# BigBus_XXL_Error.net
KiCad netlist of a schematic drawn in EAGLE
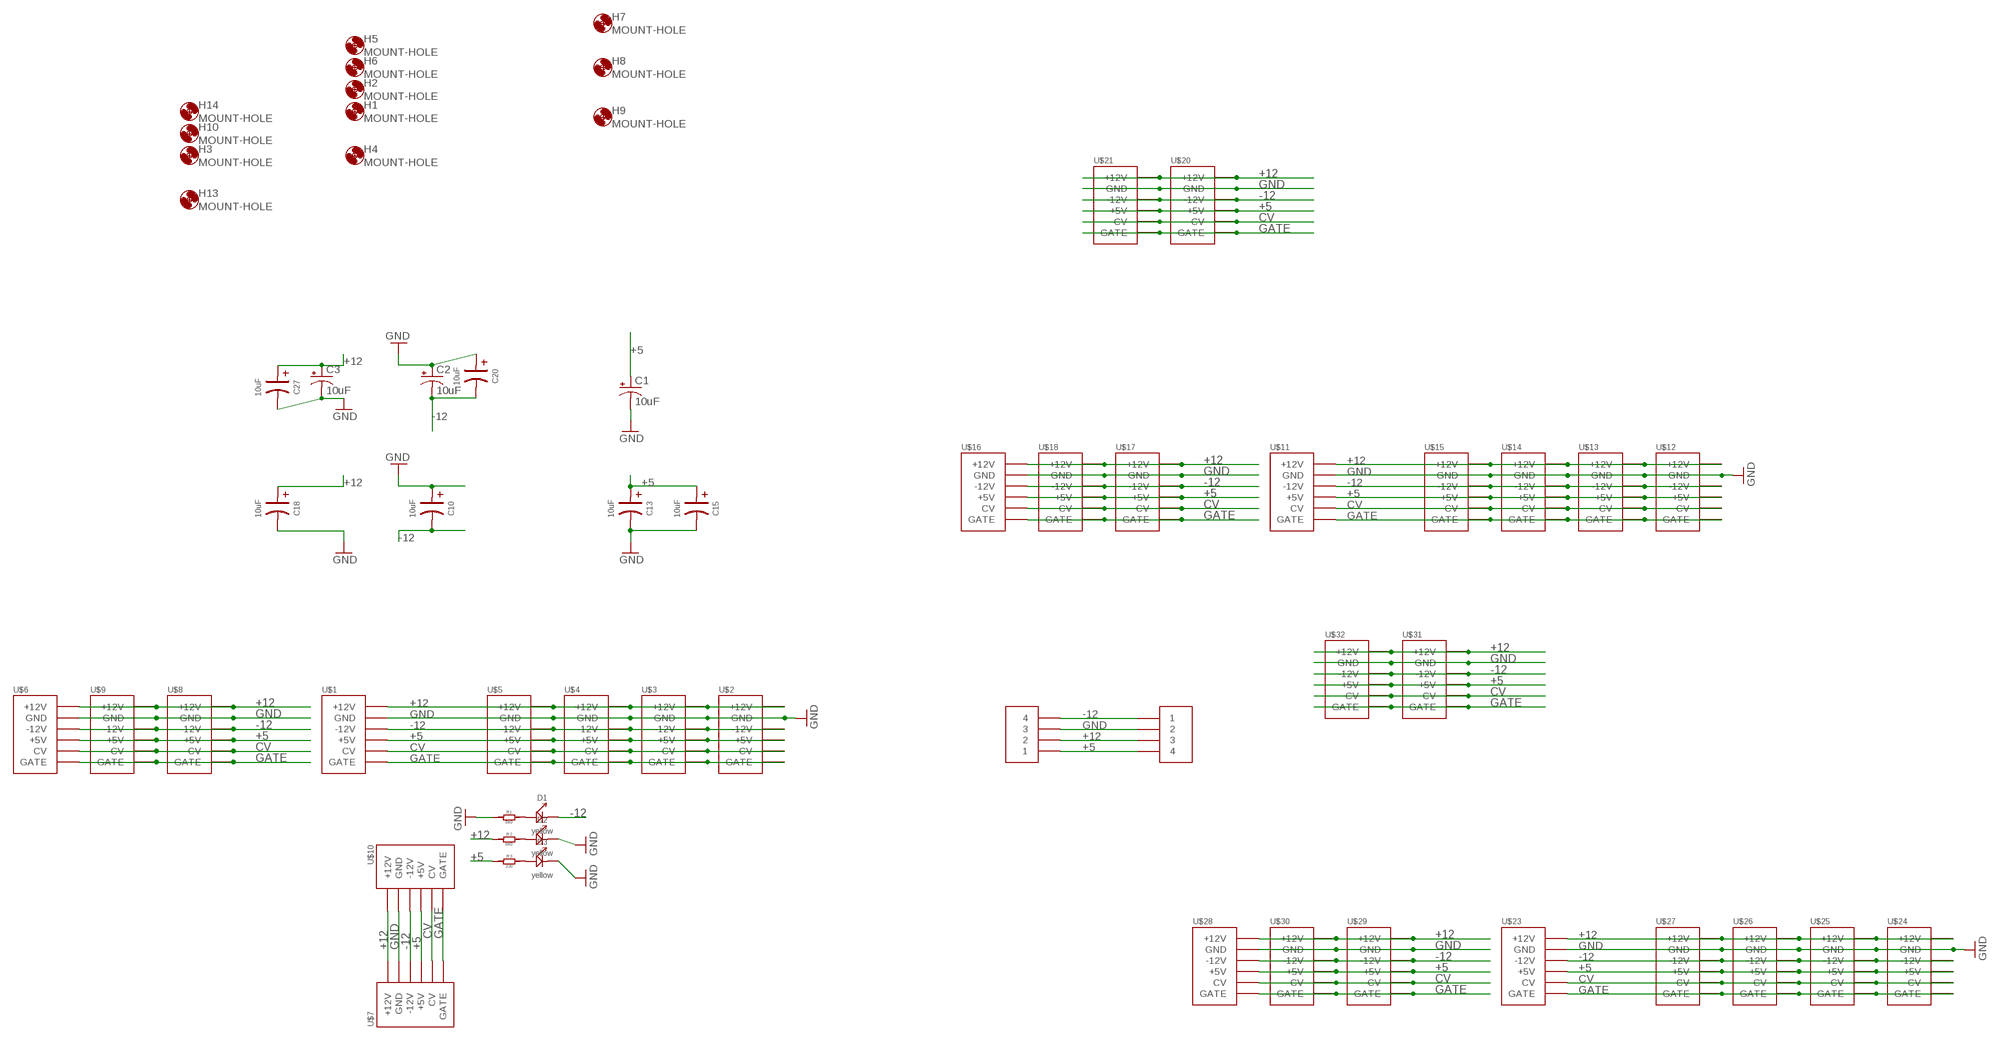
[diagram p0: schematic, sheet 1]

(export (version "E")
  (design (tool "Eeschema 10.0.6"))
  (components
    (comp (ref "C1")
      (value "10uF")
      (footprint "eagle-import:PANASONIC_D")
      (libsource (lib "eagle-import") (part "CAP_POLD"))
    )
    (comp (ref "C2")
      (value "10uF")
      (footprint "eagle-import:PANASONIC_D")
      (libsource (lib "eagle-import") (part "CAP_POLD"))
    )
    (comp (ref "C3")
      (value "10uF")
      (footprint "eagle-import:PANASONIC_D")
      (libsource (lib "eagle-import") (part "CAP_POLD"))
    )
    (comp (ref "C10")
      (value "10uF")
      (footprint "eagle-import:CASE-A_3216")
      (libsource (lib "eagle-import") (part "C-POLAR-A"))
    )
    (comp (ref "C13")
      (value "10uF")
      (footprint "eagle-import:CASE-A_3216")
      (libsource (lib "eagle-import") (part "C-POLAR-A"))
    )
    (comp (ref "C15")
      (value "10uF")
      (footprint "eagle-import:CASE-A_3216")
      (libsource (lib "eagle-import") (part "C-POLAR-A"))
    )
    (comp (ref "C18")
      (value "10uF")
      (footprint "eagle-import:CASE-A_3216")
      (libsource (lib "eagle-import") (part "C-POLAR-A"))
    )
    (comp (ref "C20")
      (value "10uF")
      (footprint "eagle-import:CASE-A_3216")
      (libsource (lib "eagle-import") (part "C-POLAR-A"))
    )
    (comp (ref "C27")
      (value "10uF")
      (footprint "eagle-import:CASE-A_3216")
      (libsource (lib "eagle-import") (part "C-POLAR-A"))
    )
    (comp (ref "D1")
      (value "yellow")
      (footprint "eagle-import:LED0603")
      (libsource (lib "eagle-import") (part "LED"))
    )
    (comp (ref "D2")
      (value "yellow")
      (footprint "eagle-import:LED0603")
      (libsource (lib "eagle-import") (part "LED"))
    )
    (comp (ref "D3")
      (value "yellow")
      (footprint "eagle-import:LED0603")
      (libsource (lib "eagle-import") (part "LED"))
    )
    (comp (ref "H1")
      (value "MOUNT-HOLE")
      (footprint "eagle-import:3.2-NOMARKINGS-SMALLSAFEZONE")
      (libsource (lib "eagle-import") (part "MOUNT-HOLE"))
    )
    (comp (ref "H2")
      (value "MOUNT-HOLE")
      (footprint "eagle-import:3.2-NOMARKINGS-SMALLSAFEZONE")
      (libsource (lib "eagle-import") (part "MOUNT-HOLE"))
    )
    (comp (ref "H3")
      (value "MOUNT-HOLE")
      (footprint "eagle-import:3.2-NOMARKINGS-SMALLSAFEZONE")
      (libsource (lib "eagle-import") (part "MOUNT-HOLE"))
    )
    (comp (ref "H4")
      (value "MOUNT-HOLE")
      (footprint "eagle-import:3.2-NOMARKINGS-SMALLSAFEZONE")
      (libsource (lib "eagle-import") (part "MOUNT-HOLE"))
    )
    (comp (ref "H5")
      (value "MOUNT-HOLE")
      (footprint "eagle-import:3.2-NOMARKINGS-SMALLSAFEZONE")
      (libsource (lib "eagle-import") (part "MOUNT-HOLE"))
    )
    (comp (ref "H6")
      (value "MOUNT-HOLE")
      (footprint "eagle-import:3.2-NOMARKINGS-SMALLSAFEZONE")
      (libsource (lib "eagle-import") (part "MOUNT-HOLE"))
    )
    (comp (ref "H7")
      (value "MOUNT-HOLE")
      (footprint "eagle-import:3.2-NOMARKINGS-SMALLSAFEZONE")
      (libsource (lib "eagle-import") (part "MOUNT-HOLE"))
    )
    (comp (ref "H8")
      (value "MOUNT-HOLE")
      (footprint "eagle-import:3.2-NOMARKINGS-SMALLSAFEZONE")
      (libsource (lib "eagle-import") (part "MOUNT-HOLE"))
    )
    (comp (ref "H9")
      (value "MOUNT-HOLE")
      (footprint "eagle-import:3.2-NOMARKINGS-SMALLSAFEZONE")
      (libsource (lib "eagle-import") (part "MOUNT-HOLE"))
    )
    (comp (ref "H10")
      (value "MOUNT-HOLE")
      (footprint "eagle-import:3.2-NOMARKINGS-SMALLSAFEZONE")
      (libsource (lib "eagle-import") (part "MOUNT-HOLE"))
    )
    (comp (ref "H13")
      (value "MOUNT-HOLE")
      (footprint "eagle-import:3.2-NOMARKINGS-SMALLSAFEZONE")
      (libsource (lib "eagle-import") (part "MOUNT-HOLE"))
    )
    (comp (ref "H14")
      (value "MOUNT-HOLE")
      (footprint "eagle-import:3.2-NOMARKINGS-SMALLSAFEZONE")
      (libsource (lib "eagle-import") (part "MOUNT-HOLE"))
    )
    (comp (ref "R1")
      (value "680")
      (footprint "eagle-import:R0603")
      (libsource (lib "eagle-import") (part "R-0603"))
    )
    (comp (ref "R2")
      (value "680")
      (footprint "eagle-import:R0603")
      (libsource (lib "eagle-import") (part "R-0603"))
    )
    (comp (ref "R3")
      (value "220")
      (footprint "eagle-import:R0603")
      (libsource (lib "eagle-import") (part "R-0603"))
    )
    (comp (ref "U$1")
      (value "POWER_SHROUDED_NOTEXT")
      (footprint "eagle-import:POWER_16_SHROUDED_NOTEXT")
      (libsource (lib "eagle-import") (part "POWER_SHROUDED_NOTEXT"))
    )
    (comp (ref "U$2")
      (value "POWER_SHROUDED_NOTEXT")
      (footprint "eagle-import:POWER_16_SHROUDED_NOTEXT")
      (libsource (lib "eagle-import") (part "POWER_SHROUDED_NOTEXT"))
    )
    (comp (ref "U$3")
      (value "POWER_SHROUDED_NOTEXT")
      (footprint "eagle-import:POWER_16_SHROUDED_NOTEXT")
      (libsource (lib "eagle-import") (part "POWER_SHROUDED_NOTEXT"))
    )
    (comp (ref "U$4")
      (value "POWER_SHROUDED_NOTEXT")
      (footprint "eagle-import:POWER_16_SHROUDED_NOTEXT")
      (libsource (lib "eagle-import") (part "POWER_SHROUDED_NOTEXT"))
    )
    (comp (ref "U$5")
      (value "POWER_SHROUDED_NOTEXT")
      (footprint "eagle-import:POWER_16_SHROUDED_NOTEXT")
      (libsource (lib "eagle-import") (part "POWER_SHROUDED_NOTEXT"))
    )
    (comp (ref "U$6")
      (value "POWER_SHROUDED_NOTEXT")
      (footprint "eagle-import:POWER_16_SHROUDED_NOTEXT")
      (libsource (lib "eagle-import") (part "POWER_SHROUDED_NOTEXT"))
    )
    (comp (ref "U$7")
      (value "POWER_SHROUDED_NOTEXT")
      (footprint "eagle-import:POWER_16_SHROUDED_NOTEXT")
      (libsource (lib "eagle-import") (part "POWER_SHROUDED_NOTEXT"))
    )
    (comp (ref "U$8")
      (value "POWER_SHROUDED_NOTEXT")
      (footprint "eagle-import:POWER_16_SHROUDED_NOTEXT")
      (libsource (lib "eagle-import") (part "POWER_SHROUDED_NOTEXT"))
    )
    (comp (ref "U$9")
      (value "POWER_SHROUDED_NOTEXT")
      (footprint "eagle-import:POWER_16_SHROUDED_NOTEXT")
      (libsource (lib "eagle-import") (part "POWER_SHROUDED_NOTEXT"))
    )
    (comp (ref "U$10")
      (value "POWER_SHROUDED_NOTEXT")
      (footprint "eagle-import:POWER_16_SHROUDED_NOTEXT")
      (libsource (lib "eagle-import") (part "POWER_SHROUDED_NOTEXT"))
    )
    (comp (ref "U$11")
      (value "POWER_SHROUDED_NOTEXT")
      (footprint "eagle-import:POWER_16_SHROUDED_NOTEXT")
      (libsource (lib "eagle-import") (part "POWER_SHROUDED_NOTEXT"))
    )
    (comp (ref "U$12")
      (value "POWER_SHROUDED_NOTEXT")
      (footprint "eagle-import:POWER_16_SHROUDED_NOTEXT")
      (libsource (lib "eagle-import") (part "POWER_SHROUDED_NOTEXT"))
    )
    (comp (ref "U$13")
      (value "POWER_SHROUDED_NOTEXT")
      (footprint "eagle-import:POWER_16_SHROUDED_NOTEXT")
      (libsource (lib "eagle-import") (part "POWER_SHROUDED_NOTEXT"))
    )
    (comp (ref "U$14")
      (value "POWER_SHROUDED_NOTEXT")
      (footprint "eagle-import:POWER_16_SHROUDED_NOTEXT")
      (libsource (lib "eagle-import") (part "POWER_SHROUDED_NOTEXT"))
    )
    (comp (ref "U$15")
      (value "POWER_SHROUDED_NOTEXT")
      (footprint "eagle-import:POWER_16_SHROUDED_NOTEXT")
      (libsource (lib "eagle-import") (part "POWER_SHROUDED_NOTEXT"))
    )
    (comp (ref "U$16")
      (value "POWER_SHROUDED_NOTEXT")
      (footprint "eagle-import:POWER_16_SHROUDED_NOTEXT")
      (libsource (lib "eagle-import") (part "POWER_SHROUDED_NOTEXT"))
    )
    (comp (ref "U$17")
      (value "POWER_SHROUDED_NOTEXT")
      (footprint "eagle-import:POWER_16_SHROUDED_NOTEXT")
      (libsource (lib "eagle-import") (part "POWER_SHROUDED_NOTEXT"))
    )
    (comp (ref "U$18")
      (value "POWER_SHROUDED_NOTEXT")
      (footprint "eagle-import:POWER_16_SHROUDED_NOTEXT")
      (libsource (lib "eagle-import") (part "POWER_SHROUDED_NOTEXT"))
    )
    (comp (ref "U$19")
      (value "4PIN5MM")
      (footprint "eagle-import:4PIN5MM")
      (libsource (lib "eagle-import") (part "4PIN5MM"))
    )
    (comp (ref "U$20")
      (value "POWER_SHROUDED_NOTEXT")
      (footprint "eagle-import:POWER_16_SHROUDED_NOTEXT")
      (libsource (lib "eagle-import") (part "POWER_SHROUDED_NOTEXT"))
    )
    (comp (ref "U$21")
      (value "POWER_SHROUDED_NOTEXT")
      (footprint "eagle-import:POWER_16_SHROUDED_NOTEXT")
      (libsource (lib "eagle-import") (part "POWER_SHROUDED_NOTEXT"))
    )
    (comp (ref "U$22")
      (value "4PIN5MM")
      (footprint "eagle-import:4PIN5MM")
      (libsource (lib "eagle-import") (part "4PIN5MM"))
    )
    (comp (ref "U$23")
      (value "POWER_SHROUDED_NOTEXT")
      (footprint "eagle-import:POWER_16_SHROUDED_NOTEXT")
      (libsource (lib "eagle-import") (part "POWER_SHROUDED_NOTEXT"))
    )
    (comp (ref "U$24")
      (value "POWER_SHROUDED_NOTEXT")
      (footprint "eagle-import:POWER_16_SHROUDED_NOTEXT")
      (libsource (lib "eagle-import") (part "POWER_SHROUDED_NOTEXT"))
    )
    (comp (ref "U$25")
      (value "POWER_SHROUDED_NOTEXT")
      (footprint "eagle-import:POWER_16_SHROUDED_NOTEXT")
      (libsource (lib "eagle-import") (part "POWER_SHROUDED_NOTEXT"))
    )
    (comp (ref "U$26")
      (value "POWER_SHROUDED_NOTEXT")
      (footprint "eagle-import:POWER_16_SHROUDED_NOTEXT")
      (libsource (lib "eagle-import") (part "POWER_SHROUDED_NOTEXT"))
    )
    (comp (ref "U$27")
      (value "POWER_SHROUDED_NOTEXT")
      (footprint "eagle-import:POWER_16_SHROUDED_NOTEXT")
      (libsource (lib "eagle-import") (part "POWER_SHROUDED_NOTEXT"))
    )
    (comp (ref "U$28")
      (value "POWER_SHROUDED_NOTEXT")
      (footprint "eagle-import:POWER_16_SHROUDED_NOTEXT")
      (libsource (lib "eagle-import") (part "POWER_SHROUDED_NOTEXT"))
    )
    (comp (ref "U$29")
      (value "POWER_SHROUDED_NOTEXT")
      (footprint "eagle-import:POWER_16_SHROUDED_NOTEXT")
      (libsource (lib "eagle-import") (part "POWER_SHROUDED_NOTEXT"))
    )
    (comp (ref "U$30")
      (value "POWER_SHROUDED_NOTEXT")
      (footprint "eagle-import:POWER_16_SHROUDED_NOTEXT")
      (libsource (lib "eagle-import") (part "POWER_SHROUDED_NOTEXT"))
    )
    (comp (ref "U$31")
      (value "POWER_SHROUDED_NOTEXT")
      (footprint "eagle-import:POWER_16_SHROUDED_NOTEXT")
      (libsource (lib "eagle-import") (part "POWER_SHROUDED_NOTEXT"))
    )
    (comp (ref "U$32")
      (value "POWER_SHROUDED_NOTEXT")
      (footprint "eagle-import:POWER_16_SHROUDED_NOTEXT")
      (libsource (lib "eagle-import") (part "POWER_SHROUDED_NOTEXT"))
    )
  )
  (nets
    (net (code "1") (name "/+5") (class "Default")
      (node (ref "C1") (pin "+") (pinfunction "+_+") (pintype "passive"))
      (node (ref "C13") (pin "+") (pinfunction "1_+") (pintype "bidirectional"))
      (node (ref "C15") (pin "+") (pinfunction "1_+") (pintype "bidirectional"))
      (node (ref "R3") (pin "1") (pinfunction "1_1") (pintype "bidirectional"))
      (node (ref "U$1") (pin "11") (pinfunction "+5V_11") (pintype "bidirectional"))
      (node (ref "U$1") (pin "12") (pinfunction "+5V_12") (pintype "bidirectional"))
      (node (ref "U$10") (pin "11") (pinfunction "+5V_11") (pintype "bidirectional"))
      (node (ref "U$10") (pin "12") (pinfunction "+5V_12") (pintype "bidirectional"))
      (node (ref "U$11") (pin "11") (pinfunction "+5V_11") (pintype "bidirectional"))
      (node (ref "U$11") (pin "12") (pinfunction "+5V_12") (pintype "bidirectional"))
      (node (ref "U$12") (pin "11") (pinfunction "+5V_11") (pintype "bidirectional"))
      (node (ref "U$12") (pin "12") (pinfunction "+5V_12") (pintype "bidirectional"))
      (node (ref "U$13") (pin "11") (pinfunction "+5V_11") (pintype "bidirectional"))
      (node (ref "U$13") (pin "12") (pinfunction "+5V_12") (pintype "bidirectional"))
      (node (ref "U$14") (pin "11") (pinfunction "+5V_11") (pintype "bidirectional"))
      (node (ref "U$14") (pin "12") (pinfunction "+5V_12") (pintype "bidirectional"))
      (node (ref "U$15") (pin "11") (pinfunction "+5V_11") (pintype "bidirectional"))
      (node (ref "U$15") (pin "12") (pinfunction "+5V_12") (pintype "bidirectional"))
      (node (ref "U$16") (pin "11") (pinfunction "+5V_11") (pintype "bidirectional"))
      (node (ref "U$16") (pin "12") (pinfunction "+5V_12") (pintype "bidirectional"))
      (node (ref "U$17") (pin "11") (pinfunction "+5V_11") (pintype "bidirectional"))
      (node (ref "U$17") (pin "12") (pinfunction "+5V_12") (pintype "bidirectional"))
      (node (ref "U$18") (pin "11") (pinfunction "+5V_11") (pintype "bidirectional"))
      (node (ref "U$18") (pin "12") (pinfunction "+5V_12") (pintype "bidirectional"))
      (node (ref "U$19") (pin "4") (pinfunction "4_4") (pintype "bidirectional"))
      (node (ref "U$2") (pin "11") (pinfunction "+5V_11") (pintype "bidirectional"))
      (node (ref "U$2") (pin "12") (pinfunction "+5V_12") (pintype "bidirectional"))
      (node (ref "U$20") (pin "11") (pinfunction "+5V_11") (pintype "bidirectional"))
      (node (ref "U$20") (pin "12") (pinfunction "+5V_12") (pintype "bidirectional"))
      (node (ref "U$21") (pin "11") (pinfunction "+5V_11") (pintype "bidirectional"))
      (node (ref "U$21") (pin "12") (pinfunction "+5V_12") (pintype "bidirectional"))
      (node (ref "U$22") (pin "1") (pinfunction "1_1") (pintype "bidirectional"))
      (node (ref "U$23") (pin "11") (pinfunction "+5V_11") (pintype "bidirectional"))
      (node (ref "U$23") (pin "12") (pinfunction "+5V_12") (pintype "bidirectional"))
      (node (ref "U$24") (pin "11") (pinfunction "+5V_11") (pintype "bidirectional"))
      (node (ref "U$24") (pin "12") (pinfunction "+5V_12") (pintype "bidirectional"))
      (node (ref "U$25") (pin "11") (pinfunction "+5V_11") (pintype "bidirectional"))
      (node (ref "U$25") (pin "12") (pinfunction "+5V_12") (pintype "bidirectional"))
      (node (ref "U$26") (pin "11") (pinfunction "+5V_11") (pintype "bidirectional"))
      (node (ref "U$26") (pin "12") (pinfunction "+5V_12") (pintype "bidirectional"))
      (node (ref "U$27") (pin "11") (pinfunction "+5V_11") (pintype "bidirectional"))
      (node (ref "U$27") (pin "12") (pinfunction "+5V_12") (pintype "bidirectional"))
      (node (ref "U$28") (pin "11") (pinfunction "+5V_11") (pintype "bidirectional"))
      (node (ref "U$28") (pin "12") (pinfunction "+5V_12") (pintype "bidirectional"))
      (node (ref "U$29") (pin "11") (pinfunction "+5V_11") (pintype "bidirectional"))
      (node (ref "U$29") (pin "12") (pinfunction "+5V_12") (pintype "bidirectional"))
      (node (ref "U$3") (pin "11") (pinfunction "+5V_11") (pintype "bidirectional"))
      (node (ref "U$3") (pin "12") (pinfunction "+5V_12") (pintype "bidirectional"))
      (node (ref "U$30") (pin "11") (pinfunction "+5V_11") (pintype "bidirectional"))
      (node (ref "U$30") (pin "12") (pinfunction "+5V_12") (pintype "bidirectional"))
      (node (ref "U$31") (pin "11") (pinfunction "+5V_11") (pintype "bidirectional"))
      (node (ref "U$31") (pin "12") (pinfunction "+5V_12") (pintype "bidirectional"))
      (node (ref "U$32") (pin "11") (pinfunction "+5V_11") (pintype "bidirectional"))
      (node (ref "U$32") (pin "12") (pinfunction "+5V_12") (pintype "bidirectional"))
      (node (ref "U$4") (pin "11") (pinfunction "+5V_11") (pintype "bidirectional"))
      (node (ref "U$4") (pin "12") (pinfunction "+5V_12") (pintype "bidirectional"))
      (node (ref "U$5") (pin "11") (pinfunction "+5V_11") (pintype "bidirectional"))
      (node (ref "U$5") (pin "12") (pinfunction "+5V_12") (pintype "bidirectional"))
      (node (ref "U$6") (pin "11") (pinfunction "+5V_11") (pintype "bidirectional"))
      (node (ref "U$6") (pin "12") (pinfunction "+5V_12") (pintype "bidirectional"))
      (node (ref "U$7") (pin "11") (pinfunction "+5V_11") (pintype "bidirectional"))
      (node (ref "U$7") (pin "12") (pinfunction "+5V_12") (pintype "bidirectional"))
      (node (ref "U$8") (pin "11") (pinfunction "+5V_11") (pintype "bidirectional"))
      (node (ref "U$8") (pin "12") (pinfunction "+5V_12") (pintype "bidirectional"))
      (node (ref "U$9") (pin "11") (pinfunction "+5V_11") (pintype "bidirectional"))
      (node (ref "U$9") (pin "12") (pinfunction "+5V_12") (pintype "bidirectional"))
    )
    (net (code "2") (name "/+12") (class "Default")
      (node (ref "C18") (pin "+") (pinfunction "1_+") (pintype "bidirectional"))
      (node (ref "C27") (pin "+") (pinfunction "1_+") (pintype "bidirectional"))
      (node (ref "C3") (pin "+") (pinfunction "+_+") (pintype "passive"))
      (node (ref "R2") (pin "1") (pinfunction "1_1") (pintype "bidirectional"))
      (node (ref "U$1") (pin "10") (pinfunction "+12V_10") (pintype "bidirectional"))
      (node (ref "U$1") (pin "9") (pinfunction "+12V_9") (pintype "bidirectional"))
      (node (ref "U$10") (pin "10") (pinfunction "+12V_10") (pintype "bidirectional"))
      (node (ref "U$10") (pin "9") (pinfunction "+12V_9") (pintype "bidirectional"))
      (node (ref "U$11") (pin "10") (pinfunction "+12V_10") (pintype "bidirectional"))
      (node (ref "U$11") (pin "9") (pinfunction "+12V_9") (pintype "bidirectional"))
      (node (ref "U$12") (pin "10") (pinfunction "+12V_10") (pintype "bidirectional"))
      (node (ref "U$12") (pin "9") (pinfunction "+12V_9") (pintype "bidirectional"))
      (node (ref "U$13") (pin "10") (pinfunction "+12V_10") (pintype "bidirectional"))
      (node (ref "U$13") (pin "9") (pinfunction "+12V_9") (pintype "bidirectional"))
      (node (ref "U$14") (pin "10") (pinfunction "+12V_10") (pintype "bidirectional"))
      (node (ref "U$14") (pin "9") (pinfunction "+12V_9") (pintype "bidirectional"))
      (node (ref "U$15") (pin "10") (pinfunction "+12V_10") (pintype "bidirectional"))
      (node (ref "U$15") (pin "9") (pinfunction "+12V_9") (pintype "bidirectional"))
      (node (ref "U$16") (pin "10") (pinfunction "+12V_10") (pintype "bidirectional"))
      (node (ref "U$16") (pin "9") (pinfunction "+12V_9") (pintype "bidirectional"))
      (node (ref "U$17") (pin "10") (pinfunction "+12V_10") (pintype "bidirectional"))
      (node (ref "U$17") (pin "9") (pinfunction "+12V_9") (pintype "bidirectional"))
      (node (ref "U$18") (pin "10") (pinfunction "+12V_10") (pintype "bidirectional"))
      (node (ref "U$18") (pin "9") (pinfunction "+12V_9") (pintype "bidirectional"))
      (node (ref "U$19") (pin "3") (pinfunction "3_3") (pintype "bidirectional"))
      (node (ref "U$2") (pin "10") (pinfunction "+12V_10") (pintype "bidirectional"))
      (node (ref "U$2") (pin "9") (pinfunction "+12V_9") (pintype "bidirectional"))
      (node (ref "U$20") (pin "10") (pinfunction "+12V_10") (pintype "bidirectional"))
      (node (ref "U$20") (pin "9") (pinfunction "+12V_9") (pintype "bidirectional"))
      (node (ref "U$21") (pin "10") (pinfunction "+12V_10") (pintype "bidirectional"))
      (node (ref "U$21") (pin "9") (pinfunction "+12V_9") (pintype "bidirectional"))
      (node (ref "U$22") (pin "2") (pinfunction "2_2") (pintype "bidirectional"))
      (node (ref "U$23") (pin "10") (pinfunction "+12V_10") (pintype "bidirectional"))
      (node (ref "U$23") (pin "9") (pinfunction "+12V_9") (pintype "bidirectional"))
      (node (ref "U$24") (pin "10") (pinfunction "+12V_10") (pintype "bidirectional"))
      (node (ref "U$24") (pin "9") (pinfunction "+12V_9") (pintype "bidirectional"))
      (node (ref "U$25") (pin "10") (pinfunction "+12V_10") (pintype "bidirectional"))
      (node (ref "U$25") (pin "9") (pinfunction "+12V_9") (pintype "bidirectional"))
      (node (ref "U$26") (pin "10") (pinfunction "+12V_10") (pintype "bidirectional"))
      (node (ref "U$26") (pin "9") (pinfunction "+12V_9") (pintype "bidirectional"))
      (node (ref "U$27") (pin "10") (pinfunction "+12V_10") (pintype "bidirectional"))
      (node (ref "U$27") (pin "9") (pinfunction "+12V_9") (pintype "bidirectional"))
      (node (ref "U$28") (pin "10") (pinfunction "+12V_10") (pintype "bidirectional"))
      (node (ref "U$28") (pin "9") (pinfunction "+12V_9") (pintype "bidirectional"))
      (node (ref "U$29") (pin "10") (pinfunction "+12V_10") (pintype "bidirectional"))
      (node (ref "U$29") (pin "9") (pinfunction "+12V_9") (pintype "bidirectional"))
      (node (ref "U$3") (pin "10") (pinfunction "+12V_10") (pintype "bidirectional"))
      (node (ref "U$3") (pin "9") (pinfunction "+12V_9") (pintype "bidirectional"))
      (node (ref "U$30") (pin "10") (pinfunction "+12V_10") (pintype "bidirectional"))
      (node (ref "U$30") (pin "9") (pinfunction "+12V_9") (pintype "bidirectional"))
      (node (ref "U$31") (pin "10") (pinfunction "+12V_10") (pintype "bidirectional"))
      (node (ref "U$31") (pin "9") (pinfunction "+12V_9") (pintype "bidirectional"))
      (node (ref "U$32") (pin "10") (pinfunction "+12V_10") (pintype "bidirectional"))
      (node (ref "U$32") (pin "9") (pinfunction "+12V_9") (pintype "bidirectional"))
      (node (ref "U$4") (pin "10") (pinfunction "+12V_10") (pintype "bidirectional"))
      (node (ref "U$4") (pin "9") (pinfunction "+12V_9") (pintype "bidirectional"))
      (node (ref "U$5") (pin "10") (pinfunction "+12V_10") (pintype "bidirectional"))
      (node (ref "U$5") (pin "9") (pinfunction "+12V_9") (pintype "bidirectional"))
      (node (ref "U$6") (pin "10") (pinfunction "+12V_10") (pintype "bidirectional"))
      (node (ref "U$6") (pin "9") (pinfunction "+12V_9") (pintype "bidirectional"))
      (node (ref "U$7") (pin "10") (pinfunction "+12V_10") (pintype "bidirectional"))
      (node (ref "U$7") (pin "9") (pinfunction "+12V_9") (pintype "bidirectional"))
      (node (ref "U$8") (pin "10") (pinfunction "+12V_10") (pintype "bidirectional"))
      (node (ref "U$8") (pin "9") (pinfunction "+12V_9") (pintype "bidirectional"))
      (node (ref "U$9") (pin "10") (pinfunction "+12V_10") (pintype "bidirectional"))
      (node (ref "U$9") (pin "9") (pinfunction "+12V_9") (pintype "bidirectional"))
    )
    (net (code "3") (name "/-12") (class "Default")
      (node (ref "C10") (pin "-") (pinfunction "2_-") (pintype "bidirectional"))
      (node (ref "C2") (pin "-") (pinfunction "-_-") (pintype "passive"))
      (node (ref "C20") (pin "-") (pinfunction "2_-") (pintype "bidirectional"))
      (node (ref "D1") (pin "-") (pinfunction "-_-") (pintype "passive"))
      (node (ref "U$1") (pin "1") (pinfunction "-12V_1") (pintype "bidirectional"))
      (node (ref "U$1") (pin "2") (pinfunction "-12V_2") (pintype "bidirectional"))
      (node (ref "U$10") (pin "1") (pinfunction "-12V_1") (pintype "bidirectional"))
      (node (ref "U$10") (pin "2") (pinfunction "-12V_2") (pintype "bidirectional"))
      (node (ref "U$11") (pin "1") (pinfunction "-12V_1") (pintype "bidirectional"))
      (node (ref "U$11") (pin "2") (pinfunction "-12V_2") (pintype "bidirectional"))
      (node (ref "U$12") (pin "1") (pinfunction "-12V_1") (pintype "bidirectional"))
      (node (ref "U$12") (pin "2") (pinfunction "-12V_2") (pintype "bidirectional"))
      (node (ref "U$13") (pin "1") (pinfunction "-12V_1") (pintype "bidirectional"))
      (node (ref "U$13") (pin "2") (pinfunction "-12V_2") (pintype "bidirectional"))
      (node (ref "U$14") (pin "1") (pinfunction "-12V_1") (pintype "bidirectional"))
      (node (ref "U$14") (pin "2") (pinfunction "-12V_2") (pintype "bidirectional"))
      (node (ref "U$15") (pin "1") (pinfunction "-12V_1") (pintype "bidirectional"))
      (node (ref "U$15") (pin "2") (pinfunction "-12V_2") (pintype "bidirectional"))
      (node (ref "U$16") (pin "1") (pinfunction "-12V_1") (pintype "bidirectional"))
      (node (ref "U$16") (pin "2") (pinfunction "-12V_2") (pintype "bidirectional"))
      (node (ref "U$17") (pin "1") (pinfunction "-12V_1") (pintype "bidirectional"))
      (node (ref "U$17") (pin "2") (pinfunction "-12V_2") (pintype "bidirectional"))
      (node (ref "U$18") (pin "1") (pinfunction "-12V_1") (pintype "bidirectional"))
      (node (ref "U$18") (pin "2") (pinfunction "-12V_2") (pintype "bidirectional"))
      (node (ref "U$19") (pin "1") (pinfunction "1_1") (pintype "bidirectional"))
      (node (ref "U$2") (pin "1") (pinfunction "-12V_1") (pintype "bidirectional"))
      (node (ref "U$2") (pin "2") (pinfunction "-12V_2") (pintype "bidirectional"))
      (node (ref "U$20") (pin "1") (pinfunction "-12V_1") (pintype "bidirectional"))
      (node (ref "U$20") (pin "2") (pinfunction "-12V_2") (pintype "bidirectional"))
      (node (ref "U$21") (pin "1") (pinfunction "-12V_1") (pintype "bidirectional"))
      (node (ref "U$21") (pin "2") (pinfunction "-12V_2") (pintype "bidirectional"))
      (node (ref "U$22") (pin "4") (pinfunction "4_4") (pintype "bidirectional"))
      (node (ref "U$23") (pin "1") (pinfunction "-12V_1") (pintype "bidirectional"))
      (node (ref "U$23") (pin "2") (pinfunction "-12V_2") (pintype "bidirectional"))
      (node (ref "U$24") (pin "1") (pinfunction "-12V_1") (pintype "bidirectional"))
      (node (ref "U$24") (pin "2") (pinfunction "-12V_2") (pintype "bidirectional"))
      (node (ref "U$25") (pin "1") (pinfunction "-12V_1") (pintype "bidirectional"))
      (node (ref "U$25") (pin "2") (pinfunction "-12V_2") (pintype "bidirectional"))
      (node (ref "U$26") (pin "1") (pinfunction "-12V_1") (pintype "bidirectional"))
      (node (ref "U$26") (pin "2") (pinfunction "-12V_2") (pintype "bidirectional"))
      (node (ref "U$27") (pin "1") (pinfunction "-12V_1") (pintype "bidirectional"))
      (node (ref "U$27") (pin "2") (pinfunction "-12V_2") (pintype "bidirectional"))
      (node (ref "U$28") (pin "1") (pinfunction "-12V_1") (pintype "bidirectional"))
      (node (ref "U$28") (pin "2") (pinfunction "-12V_2") (pintype "bidirectional"))
      (node (ref "U$29") (pin "1") (pinfunction "-12V_1") (pintype "bidirectional"))
      (node (ref "U$29") (pin "2") (pinfunction "-12V_2") (pintype "bidirectional"))
      (node (ref "U$3") (pin "1") (pinfunction "-12V_1") (pintype "bidirectional"))
      (node (ref "U$3") (pin "2") (pinfunction "-12V_2") (pintype "bidirectional"))
      (node (ref "U$30") (pin "1") (pinfunction "-12V_1") (pintype "bidirectional"))
      (node (ref "U$30") (pin "2") (pinfunction "-12V_2") (pintype "bidirectional"))
      (node (ref "U$31") (pin "1") (pinfunction "-12V_1") (pintype "bidirectional"))
      (node (ref "U$31") (pin "2") (pinfunction "-12V_2") (pintype "bidirectional"))
      (node (ref "U$32") (pin "1") (pinfunction "-12V_1") (pintype "bidirectional"))
      (node (ref "U$32") (pin "2") (pinfunction "-12V_2") (pintype "bidirectional"))
      (node (ref "U$4") (pin "1") (pinfunction "-12V_1") (pintype "bidirectional"))
      (node (ref "U$4") (pin "2") (pinfunction "-12V_2") (pintype "bidirectional"))
      (node (ref "U$5") (pin "1") (pinfunction "-12V_1") (pintype "bidirectional"))
      (node (ref "U$5") (pin "2") (pinfunction "-12V_2") (pintype "bidirectional"))
      (node (ref "U$6") (pin "1") (pinfunction "-12V_1") (pintype "bidirectional"))
      (node (ref "U$6") (pin "2") (pinfunction "-12V_2") (pintype "bidirectional"))
      (node (ref "U$7") (pin "1") (pinfunction "-12V_1") (pintype "bidirectional"))
      (node (ref "U$7") (pin "2") (pinfunction "-12V_2") (pintype "bidirectional"))
      (node (ref "U$8") (pin "1") (pinfunction "-12V_1") (pintype "bidirectional"))
      (node (ref "U$8") (pin "2") (pinfunction "-12V_2") (pintype "bidirectional"))
      (node (ref "U$9") (pin "1") (pinfunction "-12V_1") (pintype "bidirectional"))
      (node (ref "U$9") (pin "2") (pinfunction "-12V_2") (pintype "bidirectional"))
    )
    (net (code "4") (name "/CV") (class "Default")
      (node (ref "U$1") (pin "13") (pinfunction "CV_13") (pintype "bidirectional"))
      (node (ref "U$1") (pin "14") (pinfunction "CV_14") (pintype "bidirectional"))
      (node (ref "U$10") (pin "13") (pinfunction "CV_13") (pintype "bidirectional"))
      (node (ref "U$10") (pin "14") (pinfunction "CV_14") (pintype "bidirectional"))
      (node (ref "U$11") (pin "13") (pinfunction "CV_13") (pintype "bidirectional"))
      (node (ref "U$11") (pin "14") (pinfunction "CV_14") (pintype "bidirectional"))
      (node (ref "U$12") (pin "13") (pinfunction "CV_13") (pintype "bidirectional"))
      (node (ref "U$12") (pin "14") (pinfunction "CV_14") (pintype "bidirectional"))
      (node (ref "U$13") (pin "13") (pinfunction "CV_13") (pintype "bidirectional"))
      (node (ref "U$13") (pin "14") (pinfunction "CV_14") (pintype "bidirectional"))
      (node (ref "U$14") (pin "13") (pinfunction "CV_13") (pintype "bidirectional"))
      (node (ref "U$14") (pin "14") (pinfunction "CV_14") (pintype "bidirectional"))
      (node (ref "U$15") (pin "13") (pinfunction "CV_13") (pintype "bidirectional"))
      (node (ref "U$15") (pin "14") (pinfunction "CV_14") (pintype "bidirectional"))
      (node (ref "U$16") (pin "13") (pinfunction "CV_13") (pintype "bidirectional"))
      (node (ref "U$16") (pin "14") (pinfunction "CV_14") (pintype "bidirectional"))
      (node (ref "U$17") (pin "13") (pinfunction "CV_13") (pintype "bidirectional"))
      (node (ref "U$17") (pin "14") (pinfunction "CV_14") (pintype "bidirectional"))
      (node (ref "U$18") (pin "13") (pinfunction "CV_13") (pintype "bidirectional"))
      (node (ref "U$18") (pin "14") (pinfunction "CV_14") (pintype "bidirectional"))
      (node (ref "U$2") (pin "13") (pinfunction "CV_13") (pintype "bidirectional"))
      (node (ref "U$2") (pin "14") (pinfunction "CV_14") (pintype "bidirectional"))
      (node (ref "U$20") (pin "13") (pinfunction "CV_13") (pintype "bidirectional"))
      (node (ref "U$20") (pin "14") (pinfunction "CV_14") (pintype "bidirectional"))
      (node (ref "U$21") (pin "13") (pinfunction "CV_13") (pintype "bidirectional"))
      (node (ref "U$21") (pin "14") (pinfunction "CV_14") (pintype "bidirectional"))
      (node (ref "U$23") (pin "13") (pinfunction "CV_13") (pintype "bidirectional"))
      (node (ref "U$23") (pin "14") (pinfunction "CV_14") (pintype "bidirectional"))
      (node (ref "U$24") (pin "13") (pinfunction "CV_13") (pintype "bidirectional"))
      (node (ref "U$24") (pin "14") (pinfunction "CV_14") (pintype "bidirectional"))
      (node (ref "U$25") (pin "13") (pinfunction "CV_13") (pintype "bidirectional"))
      (node (ref "U$25") (pin "14") (pinfunction "CV_14") (pintype "bidirectional"))
      (node (ref "U$26") (pin "13") (pinfunction "CV_13") (pintype "bidirectional"))
      (node (ref "U$26") (pin "14") (pinfunction "CV_14") (pintype "bidirectional"))
      (node (ref "U$27") (pin "13") (pinfunction "CV_13") (pintype "bidirectional"))
      (node (ref "U$27") (pin "14") (pinfunction "CV_14") (pintype "bidirectional"))
      (node (ref "U$28") (pin "13") (pinfunction "CV_13") (pintype "bidirectional"))
      (node (ref "U$28") (pin "14") (pinfunction "CV_14") (pintype "bidirectional"))
      (node (ref "U$29") (pin "13") (pinfunction "CV_13") (pintype "bidirectional"))
      (node (ref "U$29") (pin "14") (pinfunction "CV_14") (pintype "bidirectional"))
      (node (ref "U$3") (pin "13") (pinfunction "CV_13") (pintype "bidirectional"))
      (node (ref "U$3") (pin "14") (pinfunction "CV_14") (pintype "bidirectional"))
      (node (ref "U$30") (pin "13") (pinfunction "CV_13") (pintype "bidirectional"))
      (node (ref "U$30") (pin "14") (pinfunction "CV_14") (pintype "bidirectional"))
      (node (ref "U$31") (pin "13") (pinfunction "CV_13") (pintype "bidirectional"))
      (node (ref "U$31") (pin "14") (pinfunction "CV_14") (pintype "bidirectional"))
      (node (ref "U$32") (pin "13") (pinfunction "CV_13") (pintype "bidirectional"))
      (node (ref "U$32") (pin "14") (pinfunction "CV_14") (pintype "bidirectional"))
      (node (ref "U$4") (pin "13") (pinfunction "CV_13") (pintype "bidirectional"))
      (node (ref "U$4") (pin "14") (pinfunction "CV_14") (pintype "bidirectional"))
      (node (ref "U$5") (pin "13") (pinfunction "CV_13") (pintype "bidirectional"))
      (node (ref "U$5") (pin "14") (pinfunction "CV_14") (pintype "bidirectional"))
      (node (ref "U$6") (pin "13") (pinfunction "CV_13") (pintype "bidirectional"))
      (node (ref "U$6") (pin "14") (pinfunction "CV_14") (pintype "bidirectional"))
      (node (ref "U$7") (pin "13") (pinfunction "CV_13") (pintype "bidirectional"))
      (node (ref "U$7") (pin "14") (pinfunction "CV_14") (pintype "bidirectional"))
      (node (ref "U$8") (pin "13") (pinfunction "CV_13") (pintype "bidirectional"))
      (node (ref "U$8") (pin "14") (pinfunction "CV_14") (pintype "bidirectional"))
      (node (ref "U$9") (pin "13") (pinfunction "CV_13") (pintype "bidirectional"))
      (node (ref "U$9") (pin "14") (pinfunction "CV_14") (pintype "bidirectional"))
    )
    (net (code "5") (name "/GATE") (class "Default")
      (node (ref "U$1") (pin "15") (pinfunction "GATE_15") (pintype "bidirectional"))
      (node (ref "U$1") (pin "16") (pinfunction "GATE_16") (pintype "bidirectional"))
      (node (ref "U$10") (pin "15") (pinfunction "GATE_15") (pintype "bidirectional"))
      (node (ref "U$10") (pin "16") (pinfunction "GATE_16") (pintype "bidirectional"))
      (node (ref "U$11") (pin "15") (pinfunction "GATE_15") (pintype "bidirectional"))
      (node (ref "U$11") (pin "16") (pinfunction "GATE_16") (pintype "bidirectional"))
      (node (ref "U$12") (pin "15") (pinfunction "GATE_15") (pintype "bidirectional"))
      (node (ref "U$12") (pin "16") (pinfunction "GATE_16") (pintype "bidirectional"))
      (node (ref "U$13") (pin "15") (pinfunction "GATE_15") (pintype "bidirectional"))
      (node (ref "U$13") (pin "16") (pinfunction "GATE_16") (pintype "bidirectional"))
      (node (ref "U$14") (pin "15") (pinfunction "GATE_15") (pintype "bidirectional"))
      (node (ref "U$14") (pin "16") (pinfunction "GATE_16") (pintype "bidirectional"))
      (node (ref "U$15") (pin "15") (pinfunction "GATE_15") (pintype "bidirectional"))
      (node (ref "U$15") (pin "16") (pinfunction "GATE_16") (pintype "bidirectional"))
      (node (ref "U$16") (pin "15") (pinfunction "GATE_15") (pintype "bidirectional"))
      (node (ref "U$16") (pin "16") (pinfunction "GATE_16") (pintype "bidirectional"))
      (node (ref "U$17") (pin "15") (pinfunction "GATE_15") (pintype "bidirectional"))
      (node (ref "U$17") (pin "16") (pinfunction "GATE_16") (pintype "bidirectional"))
      (node (ref "U$18") (pin "15") (pinfunction "GATE_15") (pintype "bidirectional"))
      (node (ref "U$18") (pin "16") (pinfunction "GATE_16") (pintype "bidirectional"))
      (node (ref "U$2") (pin "15") (pinfunction "GATE_15") (pintype "bidirectional"))
      (node (ref "U$2") (pin "16") (pinfunction "GATE_16") (pintype "bidirectional"))
      (node (ref "U$20") (pin "15") (pinfunction "GATE_15") (pintype "bidirectional"))
      (node (ref "U$20") (pin "16") (pinfunction "GATE_16") (pintype "bidirectional"))
      (node (ref "U$21") (pin "15") (pinfunction "GATE_15") (pintype "bidirectional"))
      (node (ref "U$21") (pin "16") (pinfunction "GATE_16") (pintype "bidirectional"))
      (node (ref "U$23") (pin "15") (pinfunction "GATE_15") (pintype "bidirectional"))
      (node (ref "U$23") (pin "16") (pinfunction "GATE_16") (pintype "bidirectional"))
      (node (ref "U$24") (pin "15") (pinfunction "GATE_15") (pintype "bidirectional"))
      (node (ref "U$24") (pin "16") (pinfunction "GATE_16") (pintype "bidirectional"))
      (node (ref "U$25") (pin "15") (pinfunction "GATE_15") (pintype "bidirectional"))
      (node (ref "U$25") (pin "16") (pinfunction "GATE_16") (pintype "bidirectional"))
      (node (ref "U$26") (pin "15") (pinfunction "GATE_15") (pintype "bidirectional"))
      (node (ref "U$26") (pin "16") (pinfunction "GATE_16") (pintype "bidirectional"))
      (node (ref "U$27") (pin "15") (pinfunction "GATE_15") (pintype "bidirectional"))
      (node (ref "U$27") (pin "16") (pinfunction "GATE_16") (pintype "bidirectional"))
      (node (ref "U$28") (pin "15") (pinfunction "GATE_15") (pintype "bidirectional"))
      (node (ref "U$28") (pin "16") (pinfunction "GATE_16") (pintype "bidirectional"))
      (node (ref "U$29") (pin "15") (pinfunction "GATE_15") (pintype "bidirectional"))
      (node (ref "U$29") (pin "16") (pinfunction "GATE_16") (pintype "bidirectional"))
      (node (ref "U$3") (pin "15") (pinfunction "GATE_15") (pintype "bidirectional"))
      (node (ref "U$3") (pin "16") (pinfunction "GATE_16") (pintype "bidirectional"))
      (node (ref "U$30") (pin "15") (pinfunction "GATE_15") (pintype "bidirectional"))
      (node (ref "U$30") (pin "16") (pinfunction "GATE_16") (pintype "bidirectional"))
      (node (ref "U$31") (pin "15") (pinfunction "GATE_15") (pintype "bidirectional"))
      (node (ref "U$31") (pin "16") (pinfunction "GATE_16") (pintype "bidirectional"))
      (node (ref "U$32") (pin "15") (pinfunction "GATE_15") (pintype "bidirectional"))
      (node (ref "U$32") (pin "16") (pinfunction "GATE_16") (pintype "bidirectional"))
      (node (ref "U$4") (pin "15") (pinfunction "GATE_15") (pintype "bidirectional"))
      (node (ref "U$4") (pin "16") (pinfunction "GATE_16") (pintype "bidirectional"))
      (node (ref "U$5") (pin "15") (pinfunction "GATE_15") (pintype "bidirectional"))
      (node (ref "U$5") (pin "16") (pinfunction "GATE_16") (pintype "bidirectional"))
      (node (ref "U$6") (pin "15") (pinfunction "GATE_15") (pintype "bidirectional"))
      (node (ref "U$6") (pin "16") (pinfunction "GATE_16") (pintype "bidirectional"))
      (node (ref "U$7") (pin "15") (pinfunction "GATE_15") (pintype "bidirectional"))
      (node (ref "U$7") (pin "16") (pinfunction "GATE_16") (pintype "bidirectional"))
      (node (ref "U$8") (pin "15") (pinfunction "GATE_15") (pintype "bidirectional"))
      (node (ref "U$8") (pin "16") (pinfunction "GATE_16") (pintype "bidirectional"))
      (node (ref "U$9") (pin "15") (pinfunction "GATE_15") (pintype "bidirectional"))
      (node (ref "U$9") (pin "16") (pinfunction "GATE_16") (pintype "bidirectional"))
    )
    (net (code "6") (name "GND") (class "Default")
      (node (ref "C1") (pin "-") (pinfunction "-_-") (pintype "passive"))
      (node (ref "C10") (pin "+") (pinfunction "1_+") (pintype "bidirectional"))
      (node (ref "C13") (pin "-") (pinfunction "2_-") (pintype "bidirectional"))
      (node (ref "C15") (pin "-") (pinfunction "2_-") (pintype "bidirectional"))
      (node (ref "C18") (pin "-") (pinfunction "2_-") (pintype "bidirectional"))
      (node (ref "C2") (pin "+") (pinfunction "+_+") (pintype "passive"))
      (node (ref "C20") (pin "+") (pinfunction "1_+") (pintype "bidirectional"))
      (node (ref "C27") (pin "-") (pinfunction "2_-") (pintype "bidirectional"))
      (node (ref "C3") (pin "-") (pinfunction "-_-") (pintype "passive"))
      (node (ref "D2") (pin "-") (pinfunction "-_-") (pintype "passive"))
      (node (ref "D3") (pin "-") (pinfunction "-_-") (pintype "passive"))
      (node (ref "R1") (pin "1") (pinfunction "1_1") (pintype "bidirectional"))
      (node (ref "U$1") (pin "3") (pinfunction "GND_3") (pintype "bidirectional"))
      (node (ref "U$1") (pin "4") (pinfunction "GND_4") (pintype "bidirectional"))
      (node (ref "U$1") (pin "5") (pinfunction "GND_5") (pintype "bidirectional"))
      (node (ref "U$1") (pin "6") (pinfunction "GND_6") (pintype "bidirectional"))
      (node (ref "U$1") (pin "7") (pinfunction "GND_7") (pintype "bidirectional"))
      (node (ref "U$1") (pin "8") (pinfunction "GND_8") (pintype "bidirectional"))
      (node (ref "U$10") (pin "3") (pinfunction "GND_3") (pintype "bidirectional"))
      (node (ref "U$10") (pin "4") (pinfunction "GND_4") (pintype "bidirectional"))
      (node (ref "U$10") (pin "5") (pinfunction "GND_5") (pintype "bidirectional"))
      (node (ref "U$10") (pin "6") (pinfunction "GND_6") (pintype "bidirectional"))
      (node (ref "U$10") (pin "7") (pinfunction "GND_7") (pintype "bidirectional"))
      (node (ref "U$10") (pin "8") (pinfunction "GND_8") (pintype "bidirectional"))
      (node (ref "U$11") (pin "3") (pinfunction "GND_3") (pintype "bidirectional"))
      (node (ref "U$11") (pin "4") (pinfunction "GND_4") (pintype "bidirectional"))
      (node (ref "U$11") (pin "5") (pinfunction "GND_5") (pintype "bidirectional"))
      (node (ref "U$11") (pin "6") (pinfunction "GND_6") (pintype "bidirectional"))
      (node (ref "U$11") (pin "7") (pinfunction "GND_7") (pintype "bidirectional"))
      (node (ref "U$11") (pin "8") (pinfunction "GND_8") (pintype "bidirectional"))
      (node (ref "U$12") (pin "3") (pinfunction "GND_3") (pintype "bidirectional"))
      (node (ref "U$12") (pin "4") (pinfunction "GND_4") (pintype "bidirectional"))
      (node (ref "U$12") (pin "5") (pinfunction "GND_5") (pintype "bidirectional"))
      (node (ref "U$12") (pin "6") (pinfunction "GND_6") (pintype "bidirectional"))
      (node (ref "U$12") (pin "7") (pinfunction "GND_7") (pintype "bidirectional"))
      (node (ref "U$12") (pin "8") (pinfunction "GND_8") (pintype "bidirectional"))
      (node (ref "U$13") (pin "3") (pinfunction "GND_3") (pintype "bidirectional"))
      (node (ref "U$13") (pin "4") (pinfunction "GND_4") (pintype "bidirectional"))
      (node (ref "U$13") (pin "5") (pinfunction "GND_5") (pintype "bidirectional"))
      (node (ref "U$13") (pin "6") (pinfunction "GND_6") (pintype "bidirectional"))
      (node (ref "U$13") (pin "7") (pinfunction "GND_7") (pintype "bidirectional"))
      (node (ref "U$13") (pin "8") (pinfunction "GND_8") (pintype "bidirectional"))
      (node (ref "U$14") (pin "3") (pinfunction "GND_3") (pintype "bidirectional"))
      (node (ref "U$14") (pin "4") (pinfunction "GND_4") (pintype "bidirectional"))
      (node (ref "U$14") (pin "5") (pinfunction "GND_5") (pintype "bidirectional"))
      (node (ref "U$14") (pin "6") (pinfunction "GND_6") (pintype "bidirectional"))
      (node (ref "U$14") (pin "7") (pinfunction "GND_7") (pintype "bidirectional"))
      (node (ref "U$14") (pin "8") (pinfunction "GND_8") (pintype "bidirectional"))
      (node (ref "U$15") (pin "3") (pinfunction "GND_3") (pintype "bidirectional"))
      (node (ref "U$15") (pin "4") (pinfunction "GND_4") (pintype "bidirectional"))
      (node (ref "U$15") (pin "5") (pinfunction "GND_5") (pintype "bidirectional"))
      (node (ref "U$15") (pin "6") (pinfunction "GND_6") (pintype "bidirectional"))
      (node (ref "U$15") (pin "7") (pinfunction "GND_7") (pintype "bidirectional"))
      (node (ref "U$15") (pin "8") (pinfunction "GND_8") (pintype "bidirectional"))
      (node (ref "U$16") (pin "3") (pinfunction "GND_3") (pintype "bidirectional"))
      (node (ref "U$16") (pin "4") (pinfunction "GND_4") (pintype "bidirectional"))
      (node (ref "U$16") (pin "5") (pinfunction "GND_5") (pintype "bidirectional"))
      (node (ref "U$16") (pin "6") (pinfunction "GND_6") (pintype "bidirectional"))
      (node (ref "U$16") (pin "7") (pinfunction "GND_7") (pintype "bidirectional"))
      (node (ref "U$16") (pin "8") (pinfunction "GND_8") (pintype "bidirectional"))
      (node (ref "U$17") (pin "3") (pinfunction "GND_3") (pintype "bidirectional"))
      (node (ref "U$17") (pin "4") (pinfunction "GND_4") (pintype "bidirectional"))
      (node (ref "U$17") (pin "5") (pinfunction "GND_5") (pintype "bidirectional"))
      (node (ref "U$17") (pin "6") (pinfunction "GND_6") (pintype "bidirectional"))
      (node (ref "U$17") (pin "7") (pinfunction "GND_7") (pintype "bidirectional"))
      (node (ref "U$17") (pin "8") (pinfunction "GND_8") (pintype "bidirectional"))
      (node (ref "U$18") (pin "3") (pinfunction "GND_3") (pintype "bidirectional"))
      (node (ref "U$18") (pin "4") (pinfunction "GND_4") (pintype "bidirectional"))
      (node (ref "U$18") (pin "5") (pinfunction "GND_5") (pintype "bidirectional"))
      (node (ref "U$18") (pin "6") (pinfunction "GND_6") (pintype "bidirectional"))
      (node (ref "U$18") (pin "7") (pinfunction "GND_7") (pintype "bidirectional"))
      (node (ref "U$18") (pin "8") (pinfunction "GND_8") (pintype "bidirectional"))
      (node (ref "U$19") (pin "2") (pinfunction "2_2") (pintype "bidirectional"))
      (node (ref "U$2") (pin "3") (pinfunction "GND_3") (pintype "bidirectional"))
      (node (ref "U$2") (pin "4") (pinfunction "GND_4") (pintype "bidirectional"))
      (node (ref "U$2") (pin "5") (pinfunction "GND_5") (pintype "bidirectional"))
      (node (ref "U$2") (pin "6") (pinfunction "GND_6") (pintype "bidirectional"))
      (node (ref "U$2") (pin "7") (pinfunction "GND_7") (pintype "bidirectional"))
      (node (ref "U$2") (pin "8") (pinfunction "GND_8") (pintype "bidirectional"))
      (node (ref "U$20") (pin "3") (pinfunction "GND_3") (pintype "bidirectional"))
      (node (ref "U$20") (pin "4") (pinfunction "GND_4") (pintype "bidirectional"))
      (node (ref "U$20") (pin "5") (pinfunction "GND_5") (pintype "bidirectional"))
      (node (ref "U$20") (pin "6") (pinfunction "GND_6") (pintype "bidirectional"))
      (node (ref "U$20") (pin "7") (pinfunction "GND_7") (pintype "bidirectional"))
      (node (ref "U$20") (pin "8") (pinfunction "GND_8") (pintype "bidirectional"))
      (node (ref "U$21") (pin "3") (pinfunction "GND_3") (pintype "bidirectional"))
      (node (ref "U$21") (pin "4") (pinfunction "GND_4") (pintype "bidirectional"))
      (node (ref "U$21") (pin "5") (pinfunction "GND_5") (pintype "bidirectional"))
      (node (ref "U$21") (pin "6") (pinfunction "GND_6") (pintype "bidirectional"))
      (node (ref "U$21") (pin "7") (pinfunction "GND_7") (pintype "bidirectional"))
      (node (ref "U$21") (pin "8") (pinfunction "GND_8") (pintype "bidirectional"))
      (node (ref "U$22") (pin "3") (pinfunction "3_3") (pintype "bidirectional"))
      (node (ref "U$23") (pin "3") (pinfunction "GND_3") (pintype "bidirectional"))
      (node (ref "U$23") (pin "4") (pinfunction "GND_4") (pintype "bidirectional"))
      (node (ref "U$23") (pin "5") (pinfunction "GND_5") (pintype "bidirectional"))
      (node (ref "U$23") (pin "6") (pinfunction "GND_6") (pintype "bidirectional"))
      (node (ref "U$23") (pin "7") (pinfunction "GND_7") (pintype "bidirectional"))
      (node (ref "U$23") (pin "8") (pinfunction "GND_8") (pintype "bidirectional"))
      (node (ref "U$24") (pin "3") (pinfunction "GND_3") (pintype "bidirectional"))
      (node (ref "U$24") (pin "4") (pinfunction "GND_4") (pintype "bidirectional"))
      (node (ref "U$24") (pin "5") (pinfunction "GND_5") (pintype "bidirectional"))
      (node (ref "U$24") (pin "6") (pinfunction "GND_6") (pintype "bidirectional"))
      (node (ref "U$24") (pin "7") (pinfunction "GND_7") (pintype "bidirectional"))
      (node (ref "U$24") (pin "8") (pinfunction "GND_8") (pintype "bidirectional"))
      (node (ref "U$25") (pin "3") (pinfunction "GND_3") (pintype "bidirectional"))
      (node (ref "U$25") (pin "4") (pinfunction "GND_4") (pintype "bidirectional"))
      (node (ref "U$25") (pin "5") (pinfunction "GND_5") (pintype "bidirectional"))
      (node (ref "U$25") (pin "6") (pinfunction "GND_6") (pintype "bidirectional"))
      (node (ref "U$25") (pin "7") (pinfunction "GND_7") (pintype "bidirectional"))
      (node (ref "U$25") (pin "8") (pinfunction "GND_8") (pintype "bidirectional"))
      (node (ref "U$26") (pin "3") (pinfunction "GND_3") (pintype "bidirectional"))
      (node (ref "U$26") (pin "4") (pinfunction "GND_4") (pintype "bidirectional"))
      (node (ref "U$26") (pin "5") (pinfunction "GND_5") (pintype "bidirectional"))
      (node (ref "U$26") (pin "6") (pinfunction "GND_6") (pintype "bidirectional"))
      (node (ref "U$26") (pin "7") (pinfunction "GND_7") (pintype "bidirectional"))
      (node (ref "U$26") (pin "8") (pinfunction "GND_8") (pintype "bidirectional"))
      (node (ref "U$27") (pin "3") (pinfunction "GND_3") (pintype "bidirectional"))
      (node (ref "U$27") (pin "4") (pinfunction "GND_4") (pintype "bidirectional"))
      (node (ref "U$27") (pin "5") (pinfunction "GND_5") (pintype "bidirectional"))
      (node (ref "U$27") (pin "6") (pinfunction "GND_6") (pintype "bidirectional"))
      (node (ref "U$27") (pin "7") (pinfunction "GND_7") (pintype "bidirectional"))
      (node (ref "U$27") (pin "8") (pinfunction "GND_8") (pintype "bidirectional"))
      (node (ref "U$28") (pin "3") (pinfunction "GND_3") (pintype "bidirectional"))
      (node (ref "U$28") (pin "4") (pinfunction "GND_4") (pintype "bidirectional"))
      (node (ref "U$28") (pin "5") (pinfunction "GND_5") (pintype "bidirectional"))
      (node (ref "U$28") (pin "6") (pinfunction "GND_6") (pintype "bidirectional"))
      (node (ref "U$28") (pin "7") (pinfunction "GND_7") (pintype "bidirectional"))
      (node (ref "U$28") (pin "8") (pinfunction "GND_8") (pintype "bidirectional"))
      (node (ref "U$29") (pin "3") (pinfunction "GND_3") (pintype "bidirectional"))
      (node (ref "U$29") (pin "4") (pinfunction "GND_4") (pintype "bidirectional"))
      (node (ref "U$29") (pin "5") (pinfunction "GND_5") (pintype "bidirectional"))
      (node (ref "U$29") (pin "6") (pinfunction "GND_6") (pintype "bidirectional"))
      (node (ref "U$29") (pin "7") (pinfunction "GND_7") (pintype "bidirectional"))
      (node (ref "U$29") (pin "8") (pinfunction "GND_8") (pintype "bidirectional"))
      (node (ref "U$3") (pin "3") (pinfunction "GND_3") (pintype "bidirectional"))
      (node (ref "U$3") (pin "4") (pinfunction "GND_4") (pintype "bidirectional"))
      (node (ref "U$3") (pin "5") (pinfunction "GND_5") (pintype "bidirectional"))
      (node (ref "U$3") (pin "6") (pinfunction "GND_6") (pintype "bidirectional"))
      (node (ref "U$3") (pin "7") (pinfunction "GND_7") (pintype "bidirectional"))
      (node (ref "U$3") (pin "8") (pinfunction "GND_8") (pintype "bidirectional"))
      (node (ref "U$30") (pin "3") (pinfunction "GND_3") (pintype "bidirectional"))
      (node (ref "U$30") (pin "4") (pinfunction "GND_4") (pintype "bidirectional"))
      (node (ref "U$30") (pin "5") (pinfunction "GND_5") (pintype "bidirectional"))
      (node (ref "U$30") (pin "6") (pinfunction "GND_6") (pintype "bidirectional"))
      (node (ref "U$30") (pin "7") (pinfunction "GND_7") (pintype "bidirectional"))
      (node (ref "U$30") (pin "8") (pinfunction "GND_8") (pintype "bidirectional"))
      (node (ref "U$31") (pin "3") (pinfunction "GND_3") (pintype "bidirectional"))
      (node (ref "U$31") (pin "4") (pinfunction "GND_4") (pintype "bidirectional"))
      (node (ref "U$31") (pin "5") (pinfunction "GND_5") (pintype "bidirectional"))
      (node (ref "U$31") (pin "6") (pinfunction "GND_6") (pintype "bidirectional"))
      (node (ref "U$31") (pin "7") (pinfunction "GND_7") (pintype "bidirectional"))
      (node (ref "U$31") (pin "8") (pinfunction "GND_8") (pintype "bidirectional"))
      (node (ref "U$32") (pin "3") (pinfunction "GND_3") (pintype "bidirectional"))
      (node (ref "U$32") (pin "4") (pinfunction "GND_4") (pintype "bidirectional"))
      (node (ref "U$32") (pin "5") (pinfunction "GND_5") (pintype "bidirectional"))
      (node (ref "U$32") (pin "6") (pinfunction "GND_6") (pintype "bidirectional"))
      (node (ref "U$32") (pin "7") (pinfunction "GND_7") (pintype "bidirectional"))
      (node (ref "U$32") (pin "8") (pinfunction "GND_8") (pintype "bidirectional"))
      (node (ref "U$4") (pin "3") (pinfunction "GND_3") (pintype "bidirectional"))
      (node (ref "U$4") (pin "4") (pinfunction "GND_4") (pintype "bidirectional"))
      (node (ref "U$4") (pin "5") (pinfunction "GND_5") (pintype "bidirectional"))
      (node (ref "U$4") (pin "6") (pinfunction "GND_6") (pintype "bidirectional"))
      (node (ref "U$4") (pin "7") (pinfunction "GND_7") (pintype "bidirectional"))
      (node (ref "U$4") (pin "8") (pinfunction "GND_8") (pintype "bidirectional"))
      (node (ref "U$5") (pin "3") (pinfunction "GND_3") (pintype "bidirectional"))
      (node (ref "U$5") (pin "4") (pinfunction "GND_4") (pintype "bidirectional"))
      (node (ref "U$5") (pin "5") (pinfunction "GND_5") (pintype "bidirectional"))
      (node (ref "U$5") (pin "6") (pinfunction "GND_6") (pintype "bidirectional"))
      (node (ref "U$5") (pin "7") (pinfunction "GND_7") (pintype "bidirectional"))
      (node (ref "U$5") (pin "8") (pinfunction "GND_8") (pintype "bidirectional"))
      (node (ref "U$6") (pin "3") (pinfunction "GND_3") (pintype "bidirectional"))
      (node (ref "U$6") (pin "4") (pinfunction "GND_4") (pintype "bidirectional"))
      (node (ref "U$6") (pin "5") (pinfunction "GND_5") (pintype "bidirectional"))
      (node (ref "U$6") (pin "6") (pinfunction "GND_6") (pintype "bidirectional"))
      (node (ref "U$6") (pin "7") (pinfunction "GND_7") (pintype "bidirectional"))
      (node (ref "U$6") (pin "8") (pinfunction "GND_8") (pintype "bidirectional"))
      (node (ref "U$7") (pin "3") (pinfunction "GND_3") (pintype "bidirectional"))
      (node (ref "U$7") (pin "4") (pinfunction "GND_4") (pintype "bidirectional"))
      (node (ref "U$7") (pin "5") (pinfunction "GND_5") (pintype "bidirectional"))
      (node (ref "U$7") (pin "6") (pinfunction "GND_6") (pintype "bidirectional"))
      (node (ref "U$7") (pin "7") (pinfunction "GND_7") (pintype "bidirectional"))
      (node (ref "U$7") (pin "8") (pinfunction "GND_8") (pintype "bidirectional"))
      (node (ref "U$8") (pin "3") (pinfunction "GND_3") (pintype "bidirectional"))
      (node (ref "U$8") (pin "4") (pinfunction "GND_4") (pintype "bidirectional"))
      (node (ref "U$8") (pin "5") (pinfunction "GND_5") (pintype "bidirectional"))
      (node (ref "U$8") (pin "6") (pinfunction "GND_6") (pintype "bidirectional"))
      (node (ref "U$8") (pin "7") (pinfunction "GND_7") (pintype "bidirectional"))
      (node (ref "U$8") (pin "8") (pinfunction "GND_8") (pintype "bidirectional"))
      (node (ref "U$9") (pin "3") (pinfunction "GND_3") (pintype "bidirectional"))
      (node (ref "U$9") (pin "4") (pinfunction "GND_4") (pintype "bidirectional"))
      (node (ref "U$9") (pin "5") (pinfunction "GND_5") (pintype "bidirectional"))
      (node (ref "U$9") (pin "6") (pinfunction "GND_6") (pintype "bidirectional"))
      (node (ref "U$9") (pin "7") (pinfunction "GND_7") (pintype "bidirectional"))
      (node (ref "U$9") (pin "8") (pinfunction "GND_8") (pintype "bidirectional"))
    )
    (net (code "7") (name "Net-(D1-Pad+)") (class "Default")
      (node (ref "D1") (pin "+") (pinfunction "+_+") (pintype "passive"))
      (node (ref "R1") (pin "2") (pinfunction "2_2") (pintype "bidirectional"))
    )
    (net (code "8") (name "Net-(D2-Pad+)") (class "Default")
      (node (ref "D2") (pin "+") (pinfunction "+_+") (pintype "passive"))
      (node (ref "R2") (pin "2") (pinfunction "2_2") (pintype "bidirectional"))
    )
    (net (code "9") (name "Net-(D3-Pad+)") (class "Default")
      (node (ref "D3") (pin "+") (pinfunction "+_+") (pintype "passive"))
      (node (ref "R3") (pin "2") (pinfunction "2_2") (pintype "bidirectional"))
    )
  )
)
